# LEDs.net
KiCad netlist of a schematic drawn in Altium Designer
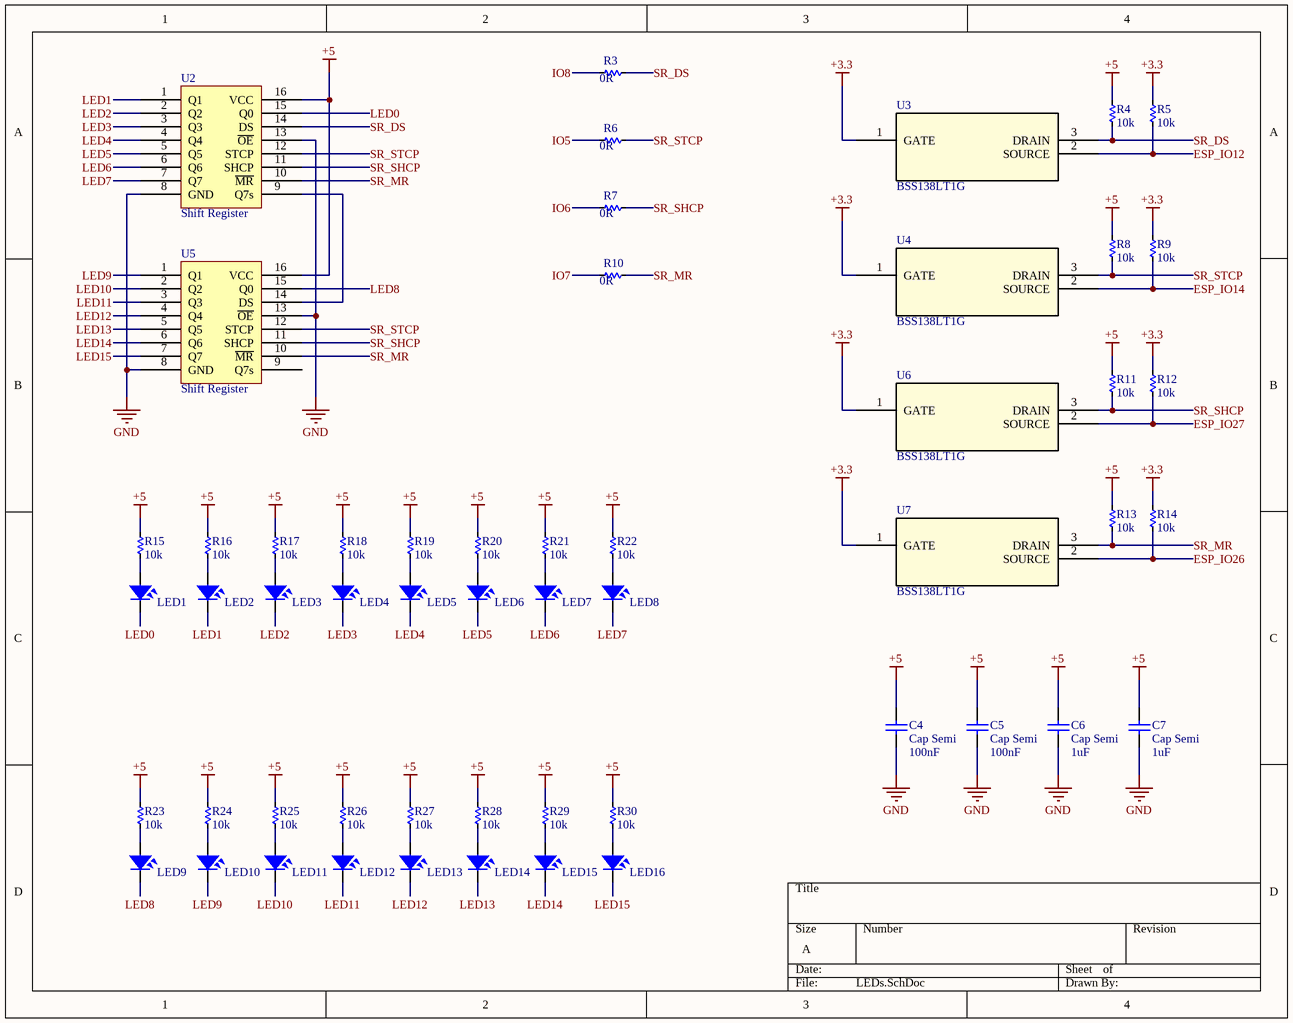
[diagram p0: LEDs.SchDoc]

(export (version "E")
  (design (tool "Eeschema 10.0.6"))
  (components
    (comp (ref "C4")
      (value "Cap Semi")
      (footprint "1608[0603]")
      (description "Capacitor (Semiconductor SIM Model)")
      (fields (field (name "ALTIUM_VALUE") "100nF") (field (name "PUBLISHER") "Altium Limited"))
      (libsource (lib "Miscellaneous Devices") (part "Cap Semi"))
    )
    (comp (ref "C5")
      (value "Cap Semi")
      (footprint "1608[0603]")
      (description "Capacitor (Semiconductor SIM Model)")
      (fields (field (name "ALTIUM_VALUE") "100nF") (field (name "PUBLISHER") "Altium Limited"))
      (libsource (lib "Miscellaneous Devices") (part "Cap Semi"))
    )
    (comp (ref "C6")
      (value "Cap Semi")
      (footprint "1608[0603]")
      (description "Capacitor (Semiconductor SIM Model)")
      (fields (field (name "ALTIUM_VALUE") "1uF") (field (name "PUBLISHER") "Altium Limited"))
      (libsource (lib "Miscellaneous Devices") (part "Cap Semi"))
    )
    (comp (ref "C7")
      (value "Cap Semi")
      (footprint "1608[0603]")
      (description "Capacitor (Semiconductor SIM Model)")
      (fields (field (name "ALTIUM_VALUE") "1uF") (field (name "PUBLISHER") "Altium Limited"))
      (libsource (lib "Miscellaneous Devices") (part "Cap Semi"))
    )
    (comp (ref "LED1") (value "LED") (footprint "LED-0805-Red") (libsource (lib "LIBRARY") (part "LED SMD")))
    (comp (ref "LED2") (value "LED") (footprint "LED-0805-Red") (libsource (lib "LIBRARY") (part "LED SMD")))
    (comp (ref "LED3") (value "LED") (footprint "LED-0805-Red") (libsource (lib "LIBRARY") (part "LED SMD")))
    (comp (ref "LED4") (value "LED") (footprint "LED-0805-Red") (libsource (lib "LIBRARY") (part "LED SMD")))
    (comp (ref "LED5") (value "LED") (footprint "LED-0805-Red") (libsource (lib "LIBRARY") (part "LED SMD")))
    (comp (ref "LED6") (value "LED") (footprint "LED-0805-Red") (libsource (lib "LIBRARY") (part "LED SMD")))
    (comp (ref "LED7") (value "LED") (footprint "LED-0805-Red") (libsource (lib "LIBRARY") (part "LED SMD")))
    (comp (ref "LED8") (value "LED") (footprint "LED-0805-Red") (libsource (lib "LIBRARY") (part "LED SMD")))
    (comp (ref "LED9") (value "LED") (footprint "LED-0805-Red") (libsource (lib "LIBRARY") (part "LED SMD")))
    (comp (ref "LED10") (value "LED") (footprint "LED-0805-Red") (libsource (lib "LIBRARY") (part "LED SMD")))
    (comp (ref "LED11") (value "LED") (footprint "LED-0805-Red") (libsource (lib "LIBRARY") (part "LED SMD")))
    (comp (ref "LED12") (value "LED") (footprint "LED-0805-Red") (libsource (lib "LIBRARY") (part "LED SMD")))
    (comp (ref "LED13") (value "LED") (footprint "LED-0805-Red") (libsource (lib "LIBRARY") (part "LED SMD")))
    (comp (ref "LED14") (value "LED") (footprint "LED-0805-Red") (libsource (lib "LIBRARY") (part "LED SMD")))
    (comp (ref "LED15") (value "LED") (footprint "LED-0805-Red") (libsource (lib "LIBRARY") (part "LED SMD")))
    (comp (ref "LED16") (value "LED") (footprint "LED-0805-Red") (libsource (lib "LIBRARY") (part "LED SMD")))
    (comp (ref "R3")
      (value "0R")
      (footprint "RES-SMD-0603")
      (description "Resistor")
      (fields
        (field (name "MANUFACTURER") "Generic Components")
        (field (name "Comment") "Res")
        (field (name "PUBLISHER") "Altium Hobart Technology Centre")
      )
      (libsource (lib "LIBRARY") (part "Res-SMD"))
    )
    (comp (ref "R4")
      (value "10k")
      (footprint "RES-SMD-0603")
      (description "Resistor")
      (fields
        (field (name "MANUFACTURER") "Generic Components")
        (field (name "Comment") "Res")
        (field (name "PUBLISHER") "Altium Hobart Technology Centre")
      )
      (libsource (lib "LIBRARY") (part "Res-SMD"))
    )
    (comp (ref "R5")
      (value "10k")
      (footprint "RES-SMD-0603")
      (description "Resistor")
      (fields
        (field (name "MANUFACTURER") "Generic Components")
        (field (name "Comment") "Res")
        (field (name "PUBLISHER") "Altium Hobart Technology Centre")
      )
      (libsource (lib "LIBRARY") (part "Res-SMD"))
    )
    (comp (ref "R6")
      (value "0R")
      (footprint "RES-SMD-0603")
      (description "Resistor")
      (fields
        (field (name "MANUFACTURER") "Generic Components")
        (field (name "Comment") "Res")
        (field (name "PUBLISHER") "Altium Hobart Technology Centre")
      )
      (libsource (lib "LIBRARY") (part "Res-SMD"))
    )
    (comp (ref "R7")
      (value "0R")
      (footprint "RES-SMD-0603")
      (description "Resistor")
      (fields
        (field (name "MANUFACTURER") "Generic Components")
        (field (name "Comment") "Res")
        (field (name "PUBLISHER") "Altium Hobart Technology Centre")
      )
      (libsource (lib "LIBRARY") (part "Res-SMD"))
    )
    (comp (ref "R8")
      (value "10k")
      (footprint "RES-SMD-0603")
      (description "Resistor")
      (fields
        (field (name "MANUFACTURER") "Generic Components")
        (field (name "Comment") "Res")
        (field (name "PUBLISHER") "Altium Hobart Technology Centre")
      )
      (libsource (lib "LIBRARY") (part "Res-SMD"))
    )
    (comp (ref "R9")
      (value "10k")
      (footprint "RES-SMD-0603")
      (description "Resistor")
      (fields
        (field (name "MANUFACTURER") "Generic Components")
        (field (name "Comment") "Res")
        (field (name "PUBLISHER") "Altium Hobart Technology Centre")
      )
      (libsource (lib "LIBRARY") (part "Res-SMD"))
    )
    (comp (ref "R10")
      (value "0R")
      (footprint "RES-SMD-0603")
      (description "Resistor")
      (fields
        (field (name "MANUFACTURER") "Generic Components")
        (field (name "Comment") "Res")
        (field (name "PUBLISHER") "Altium Hobart Technology Centre")
      )
      (libsource (lib "LIBRARY") (part "Res-SMD"))
    )
    (comp (ref "R11")
      (value "10k")
      (footprint "RES-SMD-0603")
      (description "Resistor")
      (fields
        (field (name "MANUFACTURER") "Generic Components")
        (field (name "Comment") "Res")
        (field (name "PUBLISHER") "Altium Hobart Technology Centre")
      )
      (libsource (lib "LIBRARY") (part "Res-SMD"))
    )
    (comp (ref "R12")
      (value "10k")
      (footprint "RES-SMD-0603")
      (description "Resistor")
      (fields
        (field (name "MANUFACTURER") "Generic Components")
        (field (name "Comment") "Res")
        (field (name "PUBLISHER") "Altium Hobart Technology Centre")
      )
      (libsource (lib "LIBRARY") (part "Res-SMD"))
    )
    (comp (ref "R13")
      (value "10k")
      (footprint "RES-SMD-0603")
      (description "Resistor")
      (fields
        (field (name "MANUFACTURER") "Generic Components")
        (field (name "Comment") "Res")
        (field (name "PUBLISHER") "Altium Hobart Technology Centre")
      )
      (libsource (lib "LIBRARY") (part "Res-SMD"))
    )
    (comp (ref "R14")
      (value "10k")
      (footprint "RES-SMD-0603")
      (description "Resistor")
      (fields
        (field (name "MANUFACTURER") "Generic Components")
        (field (name "Comment") "Res")
        (field (name "PUBLISHER") "Altium Hobart Technology Centre")
      )
      (libsource (lib "LIBRARY") (part "Res-SMD"))
    )
    (comp (ref "R15")
      (value "10k")
      (footprint "RES-SMD-0603")
      (description "Resistor")
      (fields
        (field (name "MANUFACTURER") "Generic Components")
        (field (name "Comment") "Res")
        (field (name "PUBLISHER") "Altium Hobart Technology Centre")
      )
      (libsource (lib "LIBRARY") (part "Res-SMD"))
    )
    (comp (ref "R16")
      (value "10k")
      (footprint "RES-SMD-0603")
      (description "Resistor")
      (fields
        (field (name "MANUFACTURER") "Generic Components")
        (field (name "Comment") "Res")
        (field (name "PUBLISHER") "Altium Hobart Technology Centre")
      )
      (libsource (lib "LIBRARY") (part "Res-SMD"))
    )
    (comp (ref "R17")
      (value "10k")
      (footprint "RES-SMD-0603")
      (description "Resistor")
      (fields
        (field (name "MANUFACTURER") "Generic Components")
        (field (name "Comment") "Res")
        (field (name "PUBLISHER") "Altium Hobart Technology Centre")
      )
      (libsource (lib "LIBRARY") (part "Res-SMD"))
    )
    (comp (ref "R18")
      (value "10k")
      (footprint "RES-SMD-0603")
      (description "Resistor")
      (fields
        (field (name "MANUFACTURER") "Generic Components")
        (field (name "Comment") "Res")
        (field (name "PUBLISHER") "Altium Hobart Technology Centre")
      )
      (libsource (lib "LIBRARY") (part "Res-SMD"))
    )
    (comp (ref "R19")
      (value "10k")
      (footprint "RES-SMD-0603")
      (description "Resistor")
      (fields
        (field (name "MANUFACTURER") "Generic Components")
        (field (name "Comment") "Res")
        (field (name "PUBLISHER") "Altium Hobart Technology Centre")
      )
      (libsource (lib "LIBRARY") (part "Res-SMD"))
    )
    (comp (ref "R20")
      (value "10k")
      (footprint "RES-SMD-0603")
      (description "Resistor")
      (fields
        (field (name "MANUFACTURER") "Generic Components")
        (field (name "Comment") "Res")
        (field (name "PUBLISHER") "Altium Hobart Technology Centre")
      )
      (libsource (lib "LIBRARY") (part "Res-SMD"))
    )
    (comp (ref "R21")
      (value "10k")
      (footprint "RES-SMD-0603")
      (description "Resistor")
      (fields
        (field (name "MANUFACTURER") "Generic Components")
        (field (name "Comment") "Res")
        (field (name "PUBLISHER") "Altium Hobart Technology Centre")
      )
      (libsource (lib "LIBRARY") (part "Res-SMD"))
    )
    (comp (ref "R22")
      (value "10k")
      (footprint "RES-SMD-0603")
      (description "Resistor")
      (fields
        (field (name "MANUFACTURER") "Generic Components")
        (field (name "Comment") "Res")
        (field (name "PUBLISHER") "Altium Hobart Technology Centre")
      )
      (libsource (lib "LIBRARY") (part "Res-SMD"))
    )
    (comp (ref "R23")
      (value "10k")
      (footprint "RES-SMD-0603")
      (description "Resistor")
      (fields
        (field (name "MANUFACTURER") "Generic Components")
        (field (name "Comment") "Res")
        (field (name "PUBLISHER") "Altium Hobart Technology Centre")
      )
      (libsource (lib "LIBRARY") (part "Res-SMD"))
    )
    (comp (ref "R24")
      (value "10k")
      (footprint "RES-SMD-0603")
      (description "Resistor")
      (fields
        (field (name "MANUFACTURER") "Generic Components")
        (field (name "Comment") "Res")
        (field (name "PUBLISHER") "Altium Hobart Technology Centre")
      )
      (libsource (lib "LIBRARY") (part "Res-SMD"))
    )
    (comp (ref "R25")
      (value "10k")
      (footprint "RES-SMD-0603")
      (description "Resistor")
      (fields
        (field (name "MANUFACTURER") "Generic Components")
        (field (name "Comment") "Res")
        (field (name "PUBLISHER") "Altium Hobart Technology Centre")
      )
      (libsource (lib "LIBRARY") (part "Res-SMD"))
    )
    (comp (ref "R26")
      (value "10k")
      (footprint "RES-SMD-0603")
      (description "Resistor")
      (fields
        (field (name "MANUFACTURER") "Generic Components")
        (field (name "Comment") "Res")
        (field (name "PUBLISHER") "Altium Hobart Technology Centre")
      )
      (libsource (lib "LIBRARY") (part "Res-SMD"))
    )
    (comp (ref "R27")
      (value "10k")
      (footprint "RES-SMD-0603")
      (description "Resistor")
      (fields
        (field (name "MANUFACTURER") "Generic Components")
        (field (name "Comment") "Res")
        (field (name "PUBLISHER") "Altium Hobart Technology Centre")
      )
      (libsource (lib "LIBRARY") (part "Res-SMD"))
    )
    (comp (ref "R28")
      (value "10k")
      (footprint "RES-SMD-0603")
      (description "Resistor")
      (fields
        (field (name "MANUFACTURER") "Generic Components")
        (field (name "Comment") "Res")
        (field (name "PUBLISHER") "Altium Hobart Technology Centre")
      )
      (libsource (lib "LIBRARY") (part "Res-SMD"))
    )
    (comp (ref "R29")
      (value "10k")
      (footprint "RES-SMD-0603")
      (description "Resistor")
      (fields
        (field (name "MANUFACTURER") "Generic Components")
        (field (name "Comment") "Res")
        (field (name "PUBLISHER") "Altium Hobart Technology Centre")
      )
      (libsource (lib "LIBRARY") (part "Res-SMD"))
    )
    (comp (ref "R30")
      (value "10k")
      (footprint "RES-SMD-0603")
      (description "Resistor")
      (fields
        (field (name "MANUFACTURER") "Generic Components")
        (field (name "Comment") "Res")
        (field (name "PUBLISHER") "Altium Hobart Technology Centre")
      )
      (libsource (lib "LIBRARY") (part "Res-SMD"))
    )
    (comp (ref "U2")
      (value "Shift Register")
      (footprint "SO16")
      (description "74HC Shift Register SOIC-16_150mil Registers ROHS")
      (libsource (lib "74HC595") (part "74HC595"))
    )
    (comp (ref "U3")
      (value "BSS138LT1G")
      (footprint "SOT23-3_ONS")
      (description "No Description Available")
      (fields (field (name "COPYRIGHT") "Copyright (C) 2018 Accelerated Designs. All rights reserved"))
      (libsource (lib "BSS138LT1G") (part "BSS138LT1G"))
    )
    (comp (ref "U4")
      (value "BSS138LT1G")
      (footprint "SOT23-3_ONS")
      (description "No Description Available")
      (fields (field (name "COPYRIGHT") "Copyright (C) 2018 Accelerated Designs. All rights reserved"))
      (libsource (lib "BSS138LT1G") (part "BSS138LT1G"))
    )
    (comp (ref "U5")
      (value "Shift Register")
      (footprint "SO16")
      (description "74HC Shift Register SOIC-16_150mil Registers ROHS")
      (libsource (lib "74HC595") (part "74HC595"))
    )
    (comp (ref "U6")
      (value "BSS138LT1G")
      (footprint "SOT23-3_ONS")
      (description "No Description Available")
      (fields (field (name "COPYRIGHT") "Copyright (C) 2018 Accelerated Designs. All rights reserved"))
      (libsource (lib "BSS138LT1G") (part "BSS138LT1G"))
    )
    (comp (ref "U7")
      (value "BSS138LT1G")
      (footprint "SOT23-3_ONS")
      (description "No Description Available")
      (fields (field (name "COPYRIGHT") "Copyright (C) 2018 Accelerated Designs. All rights reserved"))
      (libsource (lib "BSS138LT1G") (part "BSS138LT1G"))
    )
  )
  (nets
    (net (code "1") (name "+3.3") (class "Default")
      (node (ref "R12") (pin "1") (pinfunction "1_1") (pintype "passive"))
      (node (ref "R14") (pin "1") (pinfunction "1_1") (pintype "passive"))
      (node (ref "R5") (pin "1") (pinfunction "1_1") (pintype "passive"))
      (node (ref "R9") (pin "1") (pinfunction "1_1") (pintype "passive"))
      (node (ref "U3") (pin "1") (pinfunction "GATE_1") (pintype "passive"))
      (node (ref "U4") (pin "1") (pinfunction "GATE_1") (pintype "passive"))
      (node (ref "U6") (pin "1") (pinfunction "GATE_1") (pintype "passive"))
      (node (ref "U7") (pin "1") (pinfunction "GATE_1") (pintype "passive"))
    )
    (net (code "2") (name "+5") (class "Default")
      (node (ref "C4") (pin "1") (pinfunction "1_1") (pintype "passive"))
      (node (ref "C5") (pin "1") (pinfunction "1_1") (pintype "passive"))
      (node (ref "C6") (pin "1") (pinfunction "1_1") (pintype "passive"))
      (node (ref "C7") (pin "1") (pinfunction "1_1") (pintype "passive"))
      (node (ref "R11") (pin "1") (pinfunction "1_1") (pintype "passive"))
      (node (ref "R13") (pin "1") (pinfunction "1_1") (pintype "passive"))
      (node (ref "R15") (pin "1") (pinfunction "1_1") (pintype "passive"))
      (node (ref "R16") (pin "1") (pinfunction "1_1") (pintype "passive"))
      (node (ref "R17") (pin "1") (pinfunction "1_1") (pintype "passive"))
      (node (ref "R18") (pin "1") (pinfunction "1_1") (pintype "passive"))
      (node (ref "R19") (pin "1") (pinfunction "1_1") (pintype "passive"))
      (node (ref "R20") (pin "1") (pinfunction "1_1") (pintype "passive"))
      (node (ref "R21") (pin "1") (pinfunction "1_1") (pintype "passive"))
      (node (ref "R22") (pin "1") (pinfunction "1_1") (pintype "passive"))
      (node (ref "R23") (pin "1") (pinfunction "1_1") (pintype "passive"))
      (node (ref "R24") (pin "1") (pinfunction "1_1") (pintype "passive"))
      (node (ref "R25") (pin "1") (pinfunction "1_1") (pintype "passive"))
      (node (ref "R26") (pin "1") (pinfunction "1_1") (pintype "passive"))
      (node (ref "R27") (pin "1") (pinfunction "1_1") (pintype "passive"))
      (node (ref "R28") (pin "1") (pinfunction "1_1") (pintype "passive"))
      (node (ref "R29") (pin "1") (pinfunction "1_1") (pintype "passive"))
      (node (ref "R30") (pin "1") (pinfunction "1_1") (pintype "passive"))
      (node (ref "R4") (pin "1") (pinfunction "1_1") (pintype "passive"))
      (node (ref "R8") (pin "1") (pinfunction "1_1") (pintype "passive"))
      (node (ref "U2") (pin "16") (pinfunction "VCC_16") (pintype "passive"))
      (node (ref "U5") (pin "16") (pinfunction "VCC_16") (pintype "passive"))
    )
    (net (code "3") (name "/ESP_IO12") (class "Default")
      (node (ref "R5") (pin "2") (pinfunction "2_2") (pintype "passive"))
      (node (ref "U3") (pin "2") (pinfunction "SOURCE_2") (pintype "passive"))
    )
    (net (code "4") (name "/ESP_IO14") (class "Default")
      (node (ref "R9") (pin "2") (pinfunction "2_2") (pintype "passive"))
      (node (ref "U4") (pin "2") (pinfunction "SOURCE_2") (pintype "passive"))
    )
    (net (code "5") (name "/ESP_IO26") (class "Default")
      (node (ref "R14") (pin "2") (pinfunction "2_2") (pintype "passive"))
      (node (ref "U7") (pin "2") (pinfunction "SOURCE_2") (pintype "passive"))
    )
    (net (code "6") (name "/ESP_IO27") (class "Default")
      (node (ref "R12") (pin "2") (pinfunction "2_2") (pintype "passive"))
      (node (ref "U6") (pin "2") (pinfunction "SOURCE_2") (pintype "passive"))
    )
    (net (code "7") (name "/IO5") (class "Default")
      (node (ref "R6") (pin "2") (pinfunction "2_2") (pintype "passive"))
    )
    (net (code "8") (name "/IO6") (class "Default")
      (node (ref "R7") (pin "2") (pinfunction "2_2") (pintype "passive"))
    )
    (net (code "9") (name "/IO7") (class "Default")
      (node (ref "R10") (pin "2") (pinfunction "2_2") (pintype "passive"))
    )
    (net (code "10") (name "/IO8") (class "Default")
      (node (ref "R3") (pin "2") (pinfunction "2_2") (pintype "passive"))
    )
    (net (code "11") (name "/LED0") (class "Default")
      (node (ref "LED1") (pin "2") (pinfunction "2_2") (pintype "passive"))
      (node (ref "U2") (pin "15") (pinfunction "Q0_15") (pintype "passive"))
    )
    (net (code "12") (name "/LED1") (class "Default")
      (node (ref "LED2") (pin "2") (pinfunction "2_2") (pintype "passive"))
      (node (ref "U2") (pin "1") (pinfunction "Q1_1") (pintype "passive"))
    )
    (net (code "13") (name "/LED2") (class "Default")
      (node (ref "LED3") (pin "2") (pinfunction "2_2") (pintype "passive"))
      (node (ref "U2") (pin "2") (pinfunction "Q2_2") (pintype "passive"))
    )
    (net (code "14") (name "/LED3") (class "Default")
      (node (ref "LED4") (pin "2") (pinfunction "2_2") (pintype "passive"))
      (node (ref "U2") (pin "3") (pinfunction "Q3_3") (pintype "passive"))
    )
    (net (code "15") (name "/LED4") (class "Default")
      (node (ref "LED5") (pin "2") (pinfunction "2_2") (pintype "passive"))
      (node (ref "U2") (pin "4") (pinfunction "Q4_4") (pintype "passive"))
    )
    (net (code "16") (name "/LED5") (class "Default")
      (node (ref "LED6") (pin "2") (pinfunction "2_2") (pintype "passive"))
      (node (ref "U2") (pin "5") (pinfunction "Q5_5") (pintype "passive"))
    )
    (net (code "17") (name "/LED6") (class "Default")
      (node (ref "LED7") (pin "2") (pinfunction "2_2") (pintype "passive"))
      (node (ref "U2") (pin "6") (pinfunction "Q6_6") (pintype "passive"))
    )
    (net (code "18") (name "/LED7") (class "Default")
      (node (ref "LED8") (pin "2") (pinfunction "2_2") (pintype "passive"))
      (node (ref "U2") (pin "7") (pinfunction "Q7_7") (pintype "passive"))
    )
    (net (code "19") (name "/LED8") (class "Default")
      (node (ref "LED9") (pin "2") (pinfunction "2_2") (pintype "passive"))
      (node (ref "U5") (pin "15") (pinfunction "Q0_15") (pintype "passive"))
    )
    (net (code "20") (name "/LED9") (class "Default")
      (node (ref "LED10") (pin "2") (pinfunction "2_2") (pintype "passive"))
      (node (ref "U5") (pin "1") (pinfunction "Q1_1") (pintype "passive"))
    )
    (net (code "21") (name "/LED10") (class "Default")
      (node (ref "LED11") (pin "2") (pinfunction "2_2") (pintype "passive"))
      (node (ref "U5") (pin "2") (pinfunction "Q2_2") (pintype "passive"))
    )
    (net (code "22") (name "/LED11") (class "Default")
      (node (ref "LED12") (pin "2") (pinfunction "2_2") (pintype "passive"))
      (node (ref "U5") (pin "3") (pinfunction "Q3_3") (pintype "passive"))
    )
    (net (code "23") (name "/LED12") (class "Default")
      (node (ref "LED13") (pin "2") (pinfunction "2_2") (pintype "passive"))
      (node (ref "U5") (pin "4") (pinfunction "Q4_4") (pintype "passive"))
    )
    (net (code "24") (name "/LED13") (class "Default")
      (node (ref "LED14") (pin "2") (pinfunction "2_2") (pintype "passive"))
      (node (ref "U5") (pin "5") (pinfunction "Q5_5") (pintype "passive"))
    )
    (net (code "25") (name "/LED14") (class "Default")
      (node (ref "LED15") (pin "2") (pinfunction "2_2") (pintype "passive"))
      (node (ref "U5") (pin "6") (pinfunction "Q6_6") (pintype "passive"))
    )
    (net (code "26") (name "/LED15") (class "Default")
      (node (ref "LED16") (pin "2") (pinfunction "2_2") (pintype "passive"))
      (node (ref "U5") (pin "7") (pinfunction "Q7_7") (pintype "passive"))
    )
    (net (code "27") (name "/SR_DS") (class "Default")
      (node (ref "R3") (pin "1") (pinfunction "1_1") (pintype "passive"))
      (node (ref "R4") (pin "2") (pinfunction "2_2") (pintype "passive"))
      (node (ref "U2") (pin "14") (pinfunction "DS_14") (pintype "passive"))
      (node (ref "U3") (pin "3") (pinfunction "DRAIN_3") (pintype "passive"))
    )
    (net (code "28") (name "/SR_MR") (class "Default")
      (node (ref "R10") (pin "1") (pinfunction "1_1") (pintype "passive"))
      (node (ref "R13") (pin "2") (pinfunction "2_2") (pintype "passive"))
      (node (ref "U2") (pin "10") (pinfunction "~{MR}_10") (pintype "passive"))
      (node (ref "U5") (pin "10") (pinfunction "~{MR}_10") (pintype "passive"))
      (node (ref "U7") (pin "3") (pinfunction "DRAIN_3") (pintype "passive"))
    )
    (net (code "29") (name "/SR_SHCP") (class "Default")
      (node (ref "R11") (pin "2") (pinfunction "2_2") (pintype "passive"))
      (node (ref "R7") (pin "1") (pinfunction "1_1") (pintype "passive"))
      (node (ref "U2") (pin "11") (pinfunction "SHCP_11") (pintype "passive"))
      (node (ref "U5") (pin "11") (pinfunction "SHCP_11") (pintype "passive"))
      (node (ref "U6") (pin "3") (pinfunction "DRAIN_3") (pintype "passive"))
    )
    (net (code "30") (name "/SR_STCP") (class "Default")
      (node (ref "R6") (pin "1") (pinfunction "1_1") (pintype "passive"))
      (node (ref "R8") (pin "2") (pinfunction "2_2") (pintype "passive"))
      (node (ref "U2") (pin "12") (pinfunction "STCP_12") (pintype "passive"))
      (node (ref "U4") (pin "3") (pinfunction "DRAIN_3") (pintype "passive"))
      (node (ref "U5") (pin "12") (pinfunction "STCP_12") (pintype "passive"))
    )
    (net (code "31") (name "GND") (class "Default")
      (node (ref "C4") (pin "2") (pinfunction "2_2") (pintype "passive"))
      (node (ref "C5") (pin "2") (pinfunction "2_2") (pintype "passive"))
      (node (ref "C6") (pin "2") (pinfunction "2_2") (pintype "passive"))
      (node (ref "C7") (pin "2") (pinfunction "2_2") (pintype "passive"))
      (node (ref "U2") (pin "13") (pinfunction "~{OE}_13") (pintype "passive"))
      (node (ref "U2") (pin "8") (pinfunction "GND_8") (pintype "passive"))
      (node (ref "U5") (pin "13") (pinfunction "~{OE}_13") (pintype "passive"))
      (node (ref "U5") (pin "8") (pinfunction "GND_8") (pintype "passive"))
    )
    (net (code "32") (name "Net-(LED1-Pad1)") (class "Default")
      (node (ref "LED1") (pin "1") (pinfunction "1_1") (pintype "passive"))
      (node (ref "R15") (pin "2") (pinfunction "2_2") (pintype "passive"))
    )
    (net (code "33") (name "Net-(LED2-Pad1)") (class "Default")
      (node (ref "LED2") (pin "1") (pinfunction "1_1") (pintype "passive"))
      (node (ref "R16") (pin "2") (pinfunction "2_2") (pintype "passive"))
    )
    (net (code "34") (name "Net-(LED3-Pad1)") (class "Default")
      (node (ref "LED3") (pin "1") (pinfunction "1_1") (pintype "passive"))
      (node (ref "R17") (pin "2") (pinfunction "2_2") (pintype "passive"))
    )
    (net (code "35") (name "Net-(LED4-Pad1)") (class "Default")
      (node (ref "LED4") (pin "1") (pinfunction "1_1") (pintype "passive"))
      (node (ref "R18") (pin "2") (pinfunction "2_2") (pintype "passive"))
    )
    (net (code "36") (name "Net-(LED5-Pad1)") (class "Default")
      (node (ref "LED5") (pin "1") (pinfunction "1_1") (pintype "passive"))
      (node (ref "R19") (pin "2") (pinfunction "2_2") (pintype "passive"))
    )
    (net (code "37") (name "Net-(LED6-Pad1)") (class "Default")
      (node (ref "LED6") (pin "1") (pinfunction "1_1") (pintype "passive"))
      (node (ref "R20") (pin "2") (pinfunction "2_2") (pintype "passive"))
    )
    (net (code "38") (name "Net-(LED7-Pad1)") (class "Default")
      (node (ref "LED7") (pin "1") (pinfunction "1_1") (pintype "passive"))
      (node (ref "R21") (pin "2") (pinfunction "2_2") (pintype "passive"))
    )
    (net (code "39") (name "Net-(LED8-Pad1)") (class "Default")
      (node (ref "LED8") (pin "1") (pinfunction "1_1") (pintype "passive"))
      (node (ref "R22") (pin "2") (pinfunction "2_2") (pintype "passive"))
    )
    (net (code "40") (name "Net-(LED9-Pad1)") (class "Default")
      (node (ref "LED9") (pin "1") (pinfunction "1_1") (pintype "passive"))
      (node (ref "R23") (pin "2") (pinfunction "2_2") (pintype "passive"))
    )
    (net (code "41") (name "Net-(LED10-Pad1)") (class "Default")
      (node (ref "LED10") (pin "1") (pinfunction "1_1") (pintype "passive"))
      (node (ref "R24") (pin "2") (pinfunction "2_2") (pintype "passive"))
    )
    (net (code "42") (name "Net-(LED11-Pad1)") (class "Default")
      (node (ref "LED11") (pin "1") (pinfunction "1_1") (pintype "passive"))
      (node (ref "R25") (pin "2") (pinfunction "2_2") (pintype "passive"))
    )
    (net (code "43") (name "Net-(LED12-Pad1)") (class "Default")
      (node (ref "LED12") (pin "1") (pinfunction "1_1") (pintype "passive"))
      (node (ref "R26") (pin "2") (pinfunction "2_2") (pintype "passive"))
    )
    (net (code "44") (name "Net-(LED13-Pad1)") (class "Default")
      (node (ref "LED13") (pin "1") (pinfunction "1_1") (pintype "passive"))
      (node (ref "R27") (pin "2") (pinfunction "2_2") (pintype "passive"))
    )
    (net (code "45") (name "Net-(LED14-Pad1)") (class "Default")
      (node (ref "LED14") (pin "1") (pinfunction "1_1") (pintype "passive"))
      (node (ref "R28") (pin "2") (pinfunction "2_2") (pintype "passive"))
    )
    (net (code "46") (name "Net-(LED15-Pad1)") (class "Default")
      (node (ref "LED15") (pin "1") (pinfunction "1_1") (pintype "passive"))
      (node (ref "R29") (pin "2") (pinfunction "2_2") (pintype "passive"))
    )
    (net (code "47") (name "Net-(LED16-Pad1)") (class "Default")
      (node (ref "LED16") (pin "1") (pinfunction "1_1") (pintype "passive"))
      (node (ref "R30") (pin "2") (pinfunction "2_2") (pintype "passive"))
    )
    (net (code "48") (name "Net-(U2-Q7s)") (class "Default")
      (node (ref "U2") (pin "9") (pinfunction "Q7s_9") (pintype "passive"))
      (node (ref "U5") (pin "14") (pinfunction "DS_14") (pintype "passive"))
    )
    (net (code "49") (name "unconnected-(U5-Q7s-Pad9)") (class "Default")
      (node (ref "U5") (pin "9") (pinfunction "Q7s_9") (pintype "passive"))
    )
  )
)
